# YiWallet-Enc-memory.net
KiCad netlist of a schematic drawn in Altium Designer
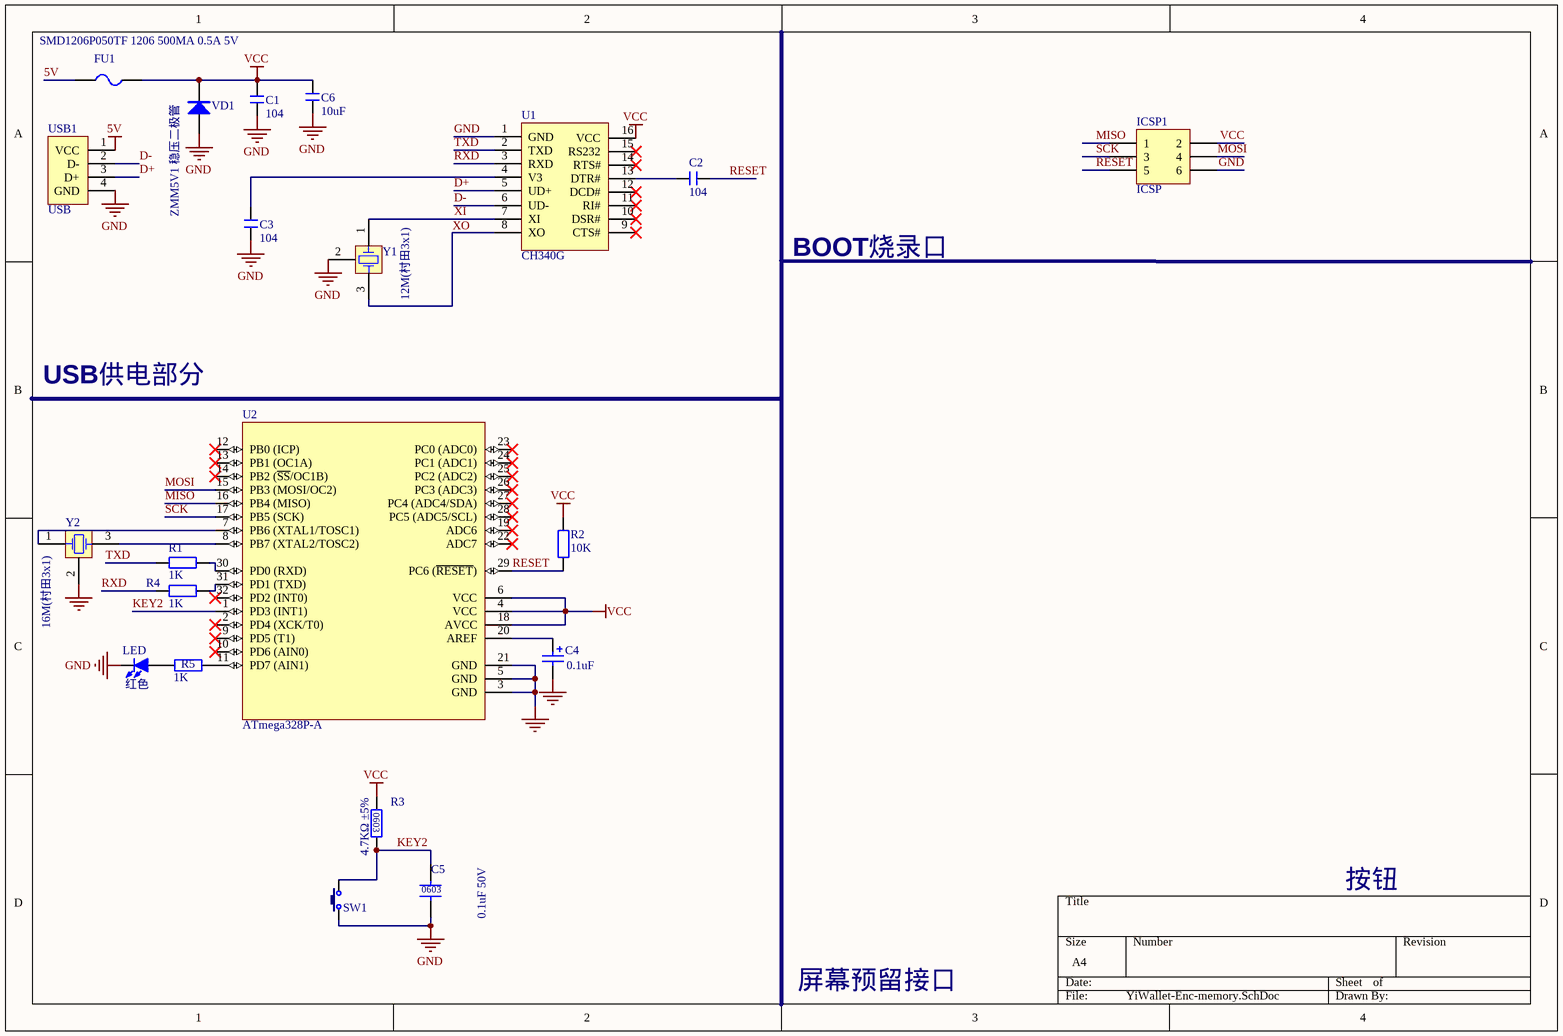
[diagram p0: YiWallet-Enc-memory.SchDoc]

(export (version "E")
  (design (tool "Eeschema 10.0.6"))
  (components
    (comp (ref "C1")
      (value "104")
      (footprint "C 0603_L")
      (description "无极性贴片电容")
      (fields (field (name "版权归属") "源创客"))
      (libsource (lib "3.1   - 电阻-电容-电感") (part "C"))
    )
    (comp (ref "C2")
      (value "104")
      (footprint "C 0603_L")
      (description "无极性贴片电容")
      (fields (field (name "版权归属") "源创客"))
      (libsource (lib "3.1   - 电阻-电容-电感") (part "C"))
    )
    (comp (ref "C3")
      (value "104")
      (footprint "C 0603_L")
      (description "无极性贴片电容")
      (fields (field (name "版权归属") "源创客"))
      (libsource (lib "3.1   - 电阻-电容-电感") (part "C"))
    )
    (comp (ref "C4")
      (value "0.1uF")
      (footprint "C 0603_L")
      (description "Polarized Capacitor (Surface Mount)")
      (fields (field (name "PUBLISHER") "Altium Limited"))
      (libsource (lib "Miscellaneous Devices") (part "Cap Pol3"))
    )
    (comp (ref "C5")
      (value "0.1uF 50V")
      (footprint "C 0603_L")
      (description "贴片电容 0.1uF 50V ±10% -55~+125℃ 0603 X7R CL10B104KB8NNNC")
      (libsource (lib "CLOU-BZ-BetaV0") (part "C-0.1uF 50V 0603"))
    )
    (comp (ref "C6")
      (value "10uF")
      (footprint "C 0603_L")
      (description "无极性贴片电容")
      (fields (field (name "版权归属") "源创客"))
      (libsource (lib "3.1   - 电阻-电容-电感") (part "C"))
    )
    (comp (ref "FU1")
      (value "SMD1206P050TF 1206 500MA 0.5A 5V")
      (footprint "FU 1206")
      (description "贴片保险丝")
      (fields (field (name "版权归属") "源创客"))
      (libsource (lib "10.1 - 保险丝-晶振") (part "FU"))
    )
    (comp (ref "ICSP1")
      (value "ICSP")
      (footprint "PH2.0-LI-6P")
      (description "Header, 3-Pin, Dual row")
      (fields (field (name "PUBLISHER") "Altium Limited"))
      (libsource (lib "Miscellaneous Connectors") (part "Header 3X2"))
    )
    (comp (ref "LED")
      (value "红色")
      (footprint "LED 0603G")
      (description "贴片LED")
      (fields (field (name "版权归属") "源创客"))
      (libsource (lib "9.1   - LED") (part "LED-SMD"))
    )
    (comp (ref "R1")
      (value "1K")
      (footprint "R 0603_L")
      (description "贴片电阻")
      (fields (field (name "版权归属") "源创客"))
      (libsource (lib "3.1   - 电阻-电容-电感") (part "R"))
    )
    (comp (ref "R2")
      (value "10K")
      (footprint "R 0603_L")
      (description "贴片电阻")
      (fields (field (name "版权归属") "源创客"))
      (libsource (lib "3.1   - 电阻-电容-电感") (part "R"))
    )
    (comp (ref "R3")
      (value "4.7KΩ ±5%")
      (footprint "C 0603_L")
      (description "贴片电阻 4.7KΩ 1/10W ±5% ±200ppm 0603")
      (libsource (lib "CLOU-BZ-BetaV0") (part "R-4K7 0603 5%"))
    )
    (comp (ref "R4")
      (value "1K")
      (footprint "R 0603_L")
      (description "贴片电阻")
      (fields (field (name "版权归属") "源创客"))
      (libsource (lib "3.1   - 电阻-电容-电感") (part "R"))
    )
    (comp (ref "R5")
      (value "1K")
      (footprint "R 0603_L")
      (description "贴片电阻")
      (fields (field (name "版权归属") "源创客"))
      (libsource (lib "3.1   - 电阻-电容-电感") (part "R"))
    )
    (comp (ref "SW1")
      (value "3x6x5")
      (footprint "TSW SMD-3*6*2.5")
      (description "3x6轻触开关")
      (fields (field (name "版权归属") "源创客"))
      (libsource (lib "5.1   - 按键-开关") (part "TSW 3x6"))
    )
    (comp (ref "U1") (value "CH340G") (footprint "SO-16") (libsource (lib "PCB_Project") (part "CH340G")))
    (comp (ref "U2")
      (value "ATmega328P-A")
      (footprint "TQFP32-7*7")
      (description "8-Bit AVR Microcontroller with 8K Bytes of In-System Programmable Flash Memory")
      (libsource (lib "Atmel Microcontroller 8-Bit AVR") (part "ATmega8-16AC"))
    )
    (comp (ref "USB1")
      (value "USB")
      (footprint "USB_A/P_A")
      (description "USB-A型公接口")
      (fields (field (name "版权归属") "源创客"))
      (libsource (lib "4.1   - 接口类") (part "USB-A/P"))
    )
    (comp (ref "VD1")
      (value "ZMM5V1 稳压二极管")
      (footprint "MINI_MELF (LL34)")
      (description "高速开关二极管")
      (fields (field (name "版权归属") "源创客"))
      (libsource (lib "8.1   - 二极管-整流桥") (part "1N4148"))
    )
    (comp (ref "Y1")
      (value "12M(村田3x1)")
      (footprint "X-CPX20")
      (description "Crystal Oscillator, 3rd In-Line Lead Version")
      (fields (field (name "PUBLISHER") "Altium Limited"))
      (libsource (lib "ECS Crystal Oscillator") (part "ECS-35-17-4-3IL"))
    )
    (comp (ref "Y2")
      (value "16M(村田3x1)")
      (footprint "X-CPX20")
      (description "Crystal Oscillator, 3rd In-Line Lead Version")
      (fields (field (name "PUBLISHER") "Altium Limited"))
      (libsource (lib "") (part "ECS-35-17-4-3IL_1"))
    )
  )
  (nets
    (net (code "1") (name "/D+") (class "Default")
      (node (ref "U1") (pin "5") (pinfunction "UD+_5") (pintype "passive"))
      (node (ref "USB1") (pin "3") (pinfunction "D+_3") (pintype "passive"))
    )
    (net (code "2") (name "/D-") (class "Default")
      (node (ref "U1") (pin "6") (pinfunction "UD-_6") (pintype "passive"))
      (node (ref "USB1") (pin "2") (pinfunction "D-_2") (pintype "passive"))
    )
    (net (code "3") (name "/KEY2") (class "Default")
      (node (ref "C5") (pin "1") (pinfunction "1_1") (pintype "passive"))
      (node (ref "R3") (pin "2") (pinfunction "2_2") (pintype "passive"))
      (node (ref "SW1") (pin "2") (pinfunction "2_2") (pintype "passive"))
      (node (ref "U2") (pin "1") (pinfunction "PD3_(INT1)_1") (pintype "bidirectional"))
    )
    (net (code "4") (name "/MISO") (class "Default")
      (node (ref "ICSP1") (pin "1") (pinfunction "1_1") (pintype "passive"))
      (node (ref "U2") (pin "16") (pinfunction "PB4_(MISO)_16") (pintype "bidirectional"))
    )
    (net (code "5") (name "/MOSI") (class "Default")
      (node (ref "ICSP1") (pin "4") (pinfunction "4_4") (pintype "passive"))
      (node (ref "U2") (pin "15") (pinfunction "PB3_(MOSI/OC2)_15") (pintype "bidirectional"))
    )
    (net (code "6") (name "/RESET") (class "Default")
      (node (ref "C2") (pin "2") (pinfunction "2_2") (pintype "passive"))
      (node (ref "ICSP1") (pin "5") (pinfunction "5_5") (pintype "passive"))
      (node (ref "R2") (pin "1") (pinfunction "1_1") (pintype "passive"))
      (node (ref "U2") (pin "29") (pinfunction "PC6_(~{RESET})_29") (pintype "bidirectional"))
    )
    (net (code "7") (name "/RXD") (class "Default")
      (node (ref "R4") (pin "2") (pinfunction "2_2") (pintype "passive"))
      (node (ref "U1") (pin "3") (pinfunction "RXD_3") (pintype "passive"))
    )
    (net (code "8") (name "/SCK") (class "Default")
      (node (ref "ICSP1") (pin "3") (pinfunction "3_3") (pintype "passive"))
      (node (ref "U2") (pin "17") (pinfunction "PB5_(SCK)_17") (pintype "bidirectional"))
    )
    (net (code "9") (name "/TXD") (class "Default")
      (node (ref "R1") (pin "2") (pinfunction "2_2") (pintype "passive"))
      (node (ref "U1") (pin "2") (pinfunction "TXD_2") (pintype "passive"))
    )
    (net (code "10") (name "/XI") (class "Default")
      (node (ref "U1") (pin "7") (pinfunction "XI_7") (pintype "passive"))
      (node (ref "Y1") (pin "1") (pinfunction "OSC1_1") (pintype "passive"))
    )
    (net (code "11") (name "/XO") (class "Default")
      (node (ref "U1") (pin "8") (pinfunction "XO_8") (pintype "passive"))
      (node (ref "Y1") (pin "3") (pinfunction "OSC2_3") (pintype "passive"))
    )
    (net (code "12") (name "5V") (class "Default")
      (node (ref "FU1") (pin "1") (pinfunction "1_1") (pintype "passive"))
      (node (ref "USB1") (pin "1") (pinfunction "VCC_1") (pintype "passive"))
    )
    (net (code "13") (name "GND") (class "Default")
      (node (ref "C1") (pin "1") (pinfunction "1_1") (pintype "passive"))
      (node (ref "C3") (pin "1") (pinfunction "1_1") (pintype "passive"))
      (node (ref "C4") (pin "2") (pinfunction "2_2") (pintype "passive"))
      (node (ref "C5") (pin "2") (pinfunction "2_2") (pintype "passive"))
      (node (ref "C6") (pin "1") (pinfunction "1_1") (pintype "passive"))
      (node (ref "ICSP1") (pin "6") (pinfunction "6_6") (pintype "passive"))
      (node (ref "LED") (pin "2") (pinfunction "K_2") (pintype "passive"))
      (node (ref "SW1") (pin "1") (pinfunction "1_1") (pintype "passive"))
      (node (ref "U1") (pin "1") (pinfunction "GND_1") (pintype "passive"))
      (node (ref "U2") (pin "21") (pinfunction "GND_21") (pintype "power_in"))
      (node (ref "U2") (pin "3") (pinfunction "GND_3") (pintype "power_in"))
      (node (ref "U2") (pin "5") (pinfunction "GND_5") (pintype "power_in"))
      (node (ref "USB1") (pin "4") (pinfunction "GND_4") (pintype "passive"))
      (node (ref "VD1") (pin "1") (pinfunction "A_1") (pintype "passive"))
      (node (ref "Y1") (pin "2") (pinfunction "COM_2") (pintype "passive"))
      (node (ref "Y2") (pin "2") (pinfunction "COM_2") (pintype "passive"))
    )
    (net (code "14") (name "Net-(LED-A)") (class "Default")
      (node (ref "LED") (pin "1") (pinfunction "A_1") (pintype "passive"))
      (node (ref "R5") (pin "2") (pinfunction "2_2") (pintype "passive"))
    )
    (net (code "15") (name "Net-(U1-DTR#)") (class "Default")
      (node (ref "C2") (pin "1") (pinfunction "1_1") (pintype "passive"))
      (node (ref "U1") (pin "13") (pinfunction "DTR#_13") (pintype "passive"))
    )
    (net (code "16") (name "Net-(U1-V3)") (class "Default")
      (node (ref "C3") (pin "2") (pinfunction "2_2") (pintype "passive"))
      (node (ref "U1") (pin "4") (pinfunction "V3_4") (pintype "passive"))
    )
    (net (code "17") (name "Net-(U2-AREF)") (class "Default")
      (node (ref "C4") (pin "1") (pinfunction "1_1") (pintype "passive"))
      (node (ref "U2") (pin "20") (pinfunction "AREF_20") (pintype "passive"))
    )
    (net (code "18") (name "Net-(U2-PB6_(XTAL1{slash}TOSC1))") (class "Default")
      (node (ref "U2") (pin "7") (pinfunction "PB6_(XTAL1/TOSC1)_7") (pintype "bidirectional"))
      (node (ref "Y2") (pin "1") (pinfunction "OSC1_1") (pintype "passive"))
    )
    (net (code "19") (name "Net-(U2-PB7_(XTAL2{slash}TOSC2))") (class "Default")
      (node (ref "U2") (pin "8") (pinfunction "PB7_(XTAL2/TOSC2)_8") (pintype "bidirectional"))
      (node (ref "Y2") (pin "3") (pinfunction "OSC2_3") (pintype "passive"))
    )
    (net (code "20") (name "Net-(U2-PD0_(RXD))") (class "Default")
      (node (ref "R1") (pin "1") (pinfunction "1_1") (pintype "passive"))
      (node (ref "U2") (pin "30") (pinfunction "PD0_(RXD)_30") (pintype "bidirectional"))
    )
    (net (code "21") (name "Net-(U2-PD1_(TXD))") (class "Default")
      (node (ref "R4") (pin "1") (pinfunction "1_1") (pintype "passive"))
      (node (ref "U2") (pin "31") (pinfunction "PD1_(TXD)_31") (pintype "bidirectional"))
    )
    (net (code "22") (name "Net-(U2-PD7_(AIN1))") (class "Default")
      (node (ref "R5") (pin "1") (pinfunction "1_1") (pintype "passive"))
      (node (ref "U2") (pin "11") (pinfunction "PD7_(AIN1)_11") (pintype "bidirectional"))
    )
    (net (code "23") (name "VCC") (class "Default")
      (node (ref "C1") (pin "2") (pinfunction "2_2") (pintype "passive"))
      (node (ref "C6") (pin "2") (pinfunction "2_2") (pintype "passive"))
      (node (ref "FU1") (pin "2") (pinfunction "2_2") (pintype "passive"))
      (node (ref "ICSP1") (pin "2") (pinfunction "2_2") (pintype "passive"))
      (node (ref "R2") (pin "2") (pinfunction "2_2") (pintype "passive"))
      (node (ref "R3") (pin "1") (pinfunction "1_1") (pintype "passive"))
      (node (ref "U1") (pin "16") (pinfunction "VCC_16") (pintype "passive"))
      (node (ref "U2") (pin "18") (pinfunction "AVCC_18") (pintype "power_in"))
      (node (ref "U2") (pin "4") (pinfunction "VCC_4") (pintype "power_in"))
      (node (ref "U2") (pin "6") (pinfunction "VCC_6") (pintype "power_in"))
      (node (ref "VD1") (pin "2") (pinfunction "K_2") (pintype "passive"))
    )
    (net (code "24") (name "unconnected-(U1-CTS#-Pad9)") (class "Default")
      (node (ref "U1") (pin "9") (pinfunction "CTS#_9") (pintype "passive+no_connect"))
    )
    (net (code "25") (name "unconnected-(U1-DCD#-Pad12)") (class "Default")
      (node (ref "U1") (pin "12") (pinfunction "DCD#_12") (pintype "passive+no_connect"))
    )
    (net (code "26") (name "unconnected-(U1-DSR#-Pad10)") (class "Default")
      (node (ref "U1") (pin "10") (pinfunction "DSR#_10") (pintype "passive+no_connect"))
    )
    (net (code "27") (name "unconnected-(U1-RI#-Pad11)") (class "Default")
      (node (ref "U1") (pin "11") (pinfunction "RI#_11") (pintype "passive+no_connect"))
    )
    (net (code "28") (name "unconnected-(U1-RS232-Pad15)") (class "Default")
      (node (ref "U1") (pin "15") (pinfunction "RS232_15") (pintype "passive+no_connect"))
    )
    (net (code "29") (name "unconnected-(U1-RTS#-Pad14)") (class "Default")
      (node (ref "U1") (pin "14") (pinfunction "RTS#_14") (pintype "passive+no_connect"))
    )
    (net (code "30") (name "unconnected-(U2-ADC6-Pad19)") (class "Default")
      (node (ref "U2") (pin "19") (pinfunction "ADC6_19") (pintype "bidirectional+no_connect"))
    )
    (net (code "31") (name "unconnected-(U2-ADC7-Pad22)") (class "Default")
      (node (ref "U2") (pin "22") (pinfunction "ADC7_22") (pintype "bidirectional+no_connect"))
    )
    (net (code "32") (name "unconnected-(U2-PB0_(ICP)-Pad12)") (class "Default")
      (node (ref "U2") (pin "12") (pinfunction "PB0_(ICP)_12") (pintype "bidirectional+no_connect"))
    )
    (net (code "33") (name "unconnected-(U2-PB1_(OC1A)-Pad13)") (class "Default")
      (node (ref "U2") (pin "13") (pinfunction "PB1_(OC1A)_13") (pintype "bidirectional+no_connect"))
    )
    (net (code "34") (name "unconnected-(U2-PB2_(~{SS}{slash}OC1B)-Pad14)") (class "Default")
      (node (ref "U2") (pin "14") (pinfunction "PB2_(~{SS}/OC1B)_14") (pintype "bidirectional+no_connect"))
    )
    (net (code "35") (name "unconnected-(U2-PC0_(ADC0)-Pad23)") (class "Default")
      (node (ref "U2") (pin "23") (pinfunction "PC0_(ADC0)_23") (pintype "bidirectional+no_connect"))
    )
    (net (code "36") (name "unconnected-(U2-PC1_(ADC1)-Pad24)") (class "Default")
      (node (ref "U2") (pin "24") (pinfunction "PC1_(ADC1)_24") (pintype "bidirectional+no_connect"))
    )
    (net (code "37") (name "unconnected-(U2-PC2_(ADC2)-Pad25)") (class "Default")
      (node (ref "U2") (pin "25") (pinfunction "PC2_(ADC2)_25") (pintype "bidirectional+no_connect"))
    )
    (net (code "38") (name "unconnected-(U2-PC3_(ADC3)-Pad26)") (class "Default")
      (node (ref "U2") (pin "26") (pinfunction "PC3_(ADC3)_26") (pintype "bidirectional+no_connect"))
    )
    (net (code "39") (name "unconnected-(U2-PC4_(ADC4{slash}SDA)-Pad27)") (class "Default")
      (node (ref "U2") (pin "27") (pinfunction "PC4_(ADC4/SDA)_27") (pintype "bidirectional+no_connect"))
    )
    (net (code "40") (name "unconnected-(U2-PC5_(ADC5{slash}SCL)-Pad28)") (class "Default")
      (node (ref "U2") (pin "28") (pinfunction "PC5_(ADC5/SCL)_28") (pintype "bidirectional+no_connect"))
    )
    (net (code "41") (name "unconnected-(U2-PD2_(INT0)-Pad32)") (class "Default")
      (node (ref "U2") (pin "32") (pinfunction "PD2_(INT0)_32") (pintype "bidirectional+no_connect"))
    )
    (net (code "42") (name "unconnected-(U2-PD4_(XCK{slash}T0)-Pad2)") (class "Default")
      (node (ref "U2") (pin "2") (pinfunction "PD4_(XCK/T0)_2") (pintype "bidirectional+no_connect"))
    )
    (net (code "43") (name "unconnected-(U2-PD5_(T1)-Pad9)") (class "Default")
      (node (ref "U2") (pin "9") (pinfunction "PD5_(T1)_9") (pintype "bidirectional+no_connect"))
    )
    (net (code "44") (name "unconnected-(U2-PD6_(AIN0)-Pad10)") (class "Default")
      (node (ref "U2") (pin "10") (pinfunction "PD6_(AIN0)_10") (pintype "bidirectional+no_connect"))
    )
  )
)
